# qre1113.net
KiCad netlist of a schematic drawn in Altium Designer
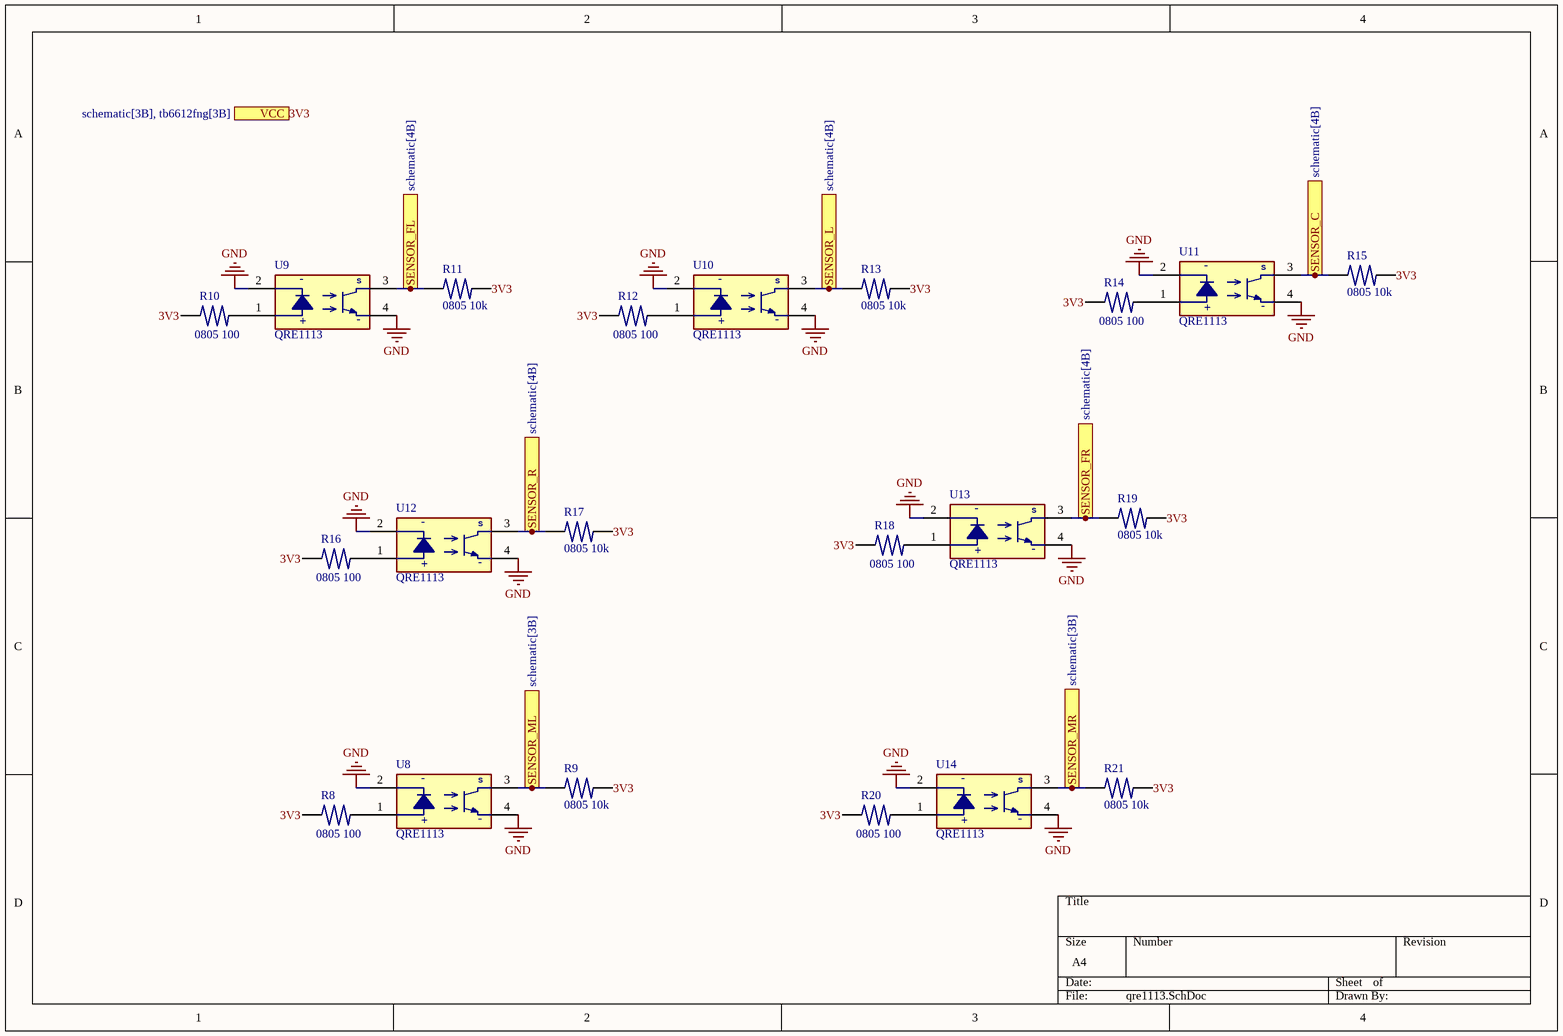
[diagram p0: qre1113.SchDoc]

(export (version "E")
  (design (tool "Eeschema 10.0.6"))
  (components
    (comp (ref "R8")
      (value "0805 100")
      (footprint "RESISTOR_0805")
      (libsource (lib "Resistors") (part "RESISTOR_0805"))
    )
    (comp (ref "R9")
      (value "0805 10k")
      (footprint "RESISTOR_0805")
      (libsource (lib "Resistors") (part "RESISTOR_0805"))
    )
    (comp (ref "R10")
      (value "0805 100")
      (footprint "RESISTOR_0805")
      (libsource (lib "Resistors") (part "RESISTOR_0805"))
    )
    (comp (ref "R11")
      (value "0805 10k")
      (footprint "RESISTOR_0805")
      (libsource (lib "Resistors") (part "RESISTOR_0805"))
    )
    (comp (ref "R12")
      (value "0805 100")
      (footprint "RESISTOR_0805")
      (libsource (lib "Resistors") (part "RESISTOR_0805"))
    )
    (comp (ref "R13")
      (value "0805 10k")
      (footprint "RESISTOR_0805")
      (libsource (lib "Resistors") (part "RESISTOR_0805"))
    )
    (comp (ref "R14")
      (value "0805 100")
      (footprint "RESISTOR_0805")
      (libsource (lib "Resistors") (part "RESISTOR_0805"))
    )
    (comp (ref "R15")
      (value "0805 10k")
      (footprint "RESISTOR_0805")
      (libsource (lib "Resistors") (part "RESISTOR_0805"))
    )
    (comp (ref "R16")
      (value "0805 100")
      (footprint "RESISTOR_0805")
      (libsource (lib "Resistors") (part "RESISTOR_0805"))
    )
    (comp (ref "R17")
      (value "0805 10k")
      (footprint "RESISTOR_0805")
      (libsource (lib "Resistors") (part "RESISTOR_0805"))
    )
    (comp (ref "R18")
      (value "0805 100")
      (footprint "RESISTOR_0805")
      (libsource (lib "Resistors") (part "RESISTOR_0805"))
    )
    (comp (ref "R19")
      (value "0805 10k")
      (footprint "RESISTOR_0805")
      (libsource (lib "Resistors") (part "RESISTOR_0805"))
    )
    (comp (ref "R20")
      (value "0805 100")
      (footprint "RESISTOR_0805")
      (libsource (lib "Resistors") (part "RESISTOR_0805"))
    )
    (comp (ref "R21")
      (value "0805 10k")
      (footprint "RESISTOR_0805")
      (libsource (lib "Resistors") (part "RESISTOR_0805"))
    )
    (comp (ref "U8")
      (value "QRE1113")
      (footprint "QRE1113")
      (description "REFLECTIVE OPTICAL SENSOR SMD")
      (libsource (lib "Sensors") (part "QRE1113"))
    )
    (comp (ref "U9")
      (value "QRE1113")
      (footprint "QRE1113")
      (description "REFLECTIVE OPTICAL SENSOR SMD")
      (libsource (lib "Sensors") (part "QRE1113"))
    )
    (comp (ref "U10")
      (value "QRE1113")
      (footprint "QRE1113")
      (description "REFLECTIVE OPTICAL SENSOR SMD")
      (libsource (lib "Sensors") (part "QRE1113"))
    )
    (comp (ref "U11")
      (value "QRE1113")
      (footprint "QRE1113")
      (description "REFLECTIVE OPTICAL SENSOR SMD")
      (libsource (lib "Sensors") (part "QRE1113"))
    )
    (comp (ref "U12")
      (value "QRE1113")
      (footprint "QRE1113")
      (description "REFLECTIVE OPTICAL SENSOR SMD")
      (libsource (lib "Sensors") (part "QRE1113"))
    )
    (comp (ref "U13")
      (value "QRE1113")
      (footprint "QRE1113")
      (description "REFLECTIVE OPTICAL SENSOR SMD")
      (libsource (lib "Sensors") (part "QRE1113"))
    )
    (comp (ref "U14")
      (value "QRE1113")
      (footprint "QRE1113")
      (description "REFLECTIVE OPTICAL SENSOR SMD")
      (libsource (lib "Sensors") (part "QRE1113"))
    )
  )
  (nets
    (net (code "1") (name "/3V3") (class "Default")
      (node (ref "R10") (pin "1") (pinfunction "1_1") (pintype "passive"))
      (node (ref "R11") (pin "2") (pinfunction "2_2") (pintype "passive"))
      (node (ref "R12") (pin "1") (pinfunction "1_1") (pintype "passive"))
      (node (ref "R13") (pin "2") (pinfunction "2_2") (pintype "passive"))
      (node (ref "R14") (pin "1") (pinfunction "1_1") (pintype "passive"))
      (node (ref "R15") (pin "2") (pinfunction "2_2") (pintype "passive"))
      (node (ref "R16") (pin "1") (pinfunction "1_1") (pintype "passive"))
      (node (ref "R17") (pin "2") (pinfunction "2_2") (pintype "passive"))
      (node (ref "R18") (pin "1") (pinfunction "1_1") (pintype "passive"))
      (node (ref "R19") (pin "2") (pinfunction "2_2") (pintype "passive"))
      (node (ref "R20") (pin "1") (pinfunction "1_1") (pintype "passive"))
      (node (ref "R21") (pin "2") (pinfunction "2_2") (pintype "passive"))
      (node (ref "R8") (pin "1") (pinfunction "1_1") (pintype "passive"))
      (node (ref "R9") (pin "2") (pinfunction "2_2") (pintype "passive"))
    )
    (net (code "2") (name "/SENSOR_C") (class "Default")
      (node (ref "R15") (pin "1") (pinfunction "1_1") (pintype "passive"))
      (node (ref "U11") (pin "3") (pinfunction "SIGNAL_3") (pintype "passive"))
    )
    (net (code "3") (name "/SENSOR_FL") (class "Default")
      (node (ref "R11") (pin "1") (pinfunction "1_1") (pintype "passive"))
      (node (ref "U9") (pin "3") (pinfunction "SIGNAL_3") (pintype "passive"))
    )
    (net (code "4") (name "/SENSOR_FR") (class "Default")
      (node (ref "R19") (pin "1") (pinfunction "1_1") (pintype "passive"))
      (node (ref "U13") (pin "3") (pinfunction "SIGNAL_3") (pintype "passive"))
    )
    (net (code "5") (name "/SENSOR_L") (class "Default")
      (node (ref "R13") (pin "1") (pinfunction "1_1") (pintype "passive"))
      (node (ref "U10") (pin "3") (pinfunction "SIGNAL_3") (pintype "passive"))
    )
    (net (code "6") (name "/SENSOR_ML") (class "Default")
      (node (ref "R9") (pin "1") (pinfunction "1_1") (pintype "passive"))
      (node (ref "U8") (pin "3") (pinfunction "SIGNAL_3") (pintype "passive"))
    )
    (net (code "7") (name "/SENSOR_MR") (class "Default")
      (node (ref "R21") (pin "1") (pinfunction "1_1") (pintype "passive"))
      (node (ref "U14") (pin "3") (pinfunction "SIGNAL_3") (pintype "passive"))
    )
    (net (code "8") (name "/SENSOR_R") (class "Default")
      (node (ref "R17") (pin "1") (pinfunction "1_1") (pintype "passive"))
      (node (ref "U12") (pin "3") (pinfunction "SIGNAL_3") (pintype "passive"))
    )
    (net (code "9") (name "GND") (class "Default")
      (node (ref "U10") (pin "2") (pinfunction "GND_2") (pintype "passive"))
      (node (ref "U10") (pin "4") (pinfunction "GND_4") (pintype "passive"))
      (node (ref "U11") (pin "2") (pinfunction "GND_2") (pintype "passive"))
      (node (ref "U11") (pin "4") (pinfunction "GND_4") (pintype "passive"))
      (node (ref "U12") (pin "2") (pinfunction "GND_2") (pintype "passive"))
      (node (ref "U12") (pin "4") (pinfunction "GND_4") (pintype "passive"))
      (node (ref "U13") (pin "2") (pinfunction "GND_2") (pintype "passive"))
      (node (ref "U13") (pin "4") (pinfunction "GND_4") (pintype "passive"))
      (node (ref "U14") (pin "2") (pinfunction "GND_2") (pintype "passive"))
      (node (ref "U14") (pin "4") (pinfunction "GND_4") (pintype "passive"))
      (node (ref "U8") (pin "2") (pinfunction "GND_2") (pintype "passive"))
      (node (ref "U8") (pin "4") (pinfunction "GND_4") (pintype "passive"))
      (node (ref "U9") (pin "2") (pinfunction "GND_2") (pintype "passive"))
      (node (ref "U9") (pin "4") (pinfunction "GND_4") (pintype "passive"))
    )
    (net (code "10") (name "Net-(U8-VCC)") (class "Default")
      (node (ref "R8") (pin "2") (pinfunction "2_2") (pintype "passive"))
      (node (ref "U8") (pin "1") (pinfunction "VCC_1") (pintype "passive"))
    )
    (net (code "11") (name "Net-(U9-VCC)") (class "Default")
      (node (ref "R10") (pin "2") (pinfunction "2_2") (pintype "passive"))
      (node (ref "U9") (pin "1") (pinfunction "VCC_1") (pintype "passive"))
    )
    (net (code "12") (name "Net-(U10-VCC)") (class "Default")
      (node (ref "R12") (pin "2") (pinfunction "2_2") (pintype "passive"))
      (node (ref "U10") (pin "1") (pinfunction "VCC_1") (pintype "passive"))
    )
    (net (code "13") (name "Net-(U11-VCC)") (class "Default")
      (node (ref "R14") (pin "2") (pinfunction "2_2") (pintype "passive"))
      (node (ref "U11") (pin "1") (pinfunction "VCC_1") (pintype "passive"))
    )
    (net (code "14") (name "Net-(U12-VCC)") (class "Default")
      (node (ref "R16") (pin "2") (pinfunction "2_2") (pintype "passive"))
      (node (ref "U12") (pin "1") (pinfunction "VCC_1") (pintype "passive"))
    )
    (net (code "15") (name "Net-(U13-VCC)") (class "Default")
      (node (ref "R18") (pin "2") (pinfunction "2_2") (pintype "passive"))
      (node (ref "U13") (pin "1") (pinfunction "VCC_1") (pintype "passive"))
    )
    (net (code "16") (name "Net-(U14-VCC)") (class "Default")
      (node (ref "R20") (pin "2") (pinfunction "2_2") (pintype "passive"))
      (node (ref "U14") (pin "1") (pinfunction "VCC_1") (pintype "passive"))
    )
  )
)
